# Discharge.net
KiCad netlist of a schematic drawn in Altium Designer
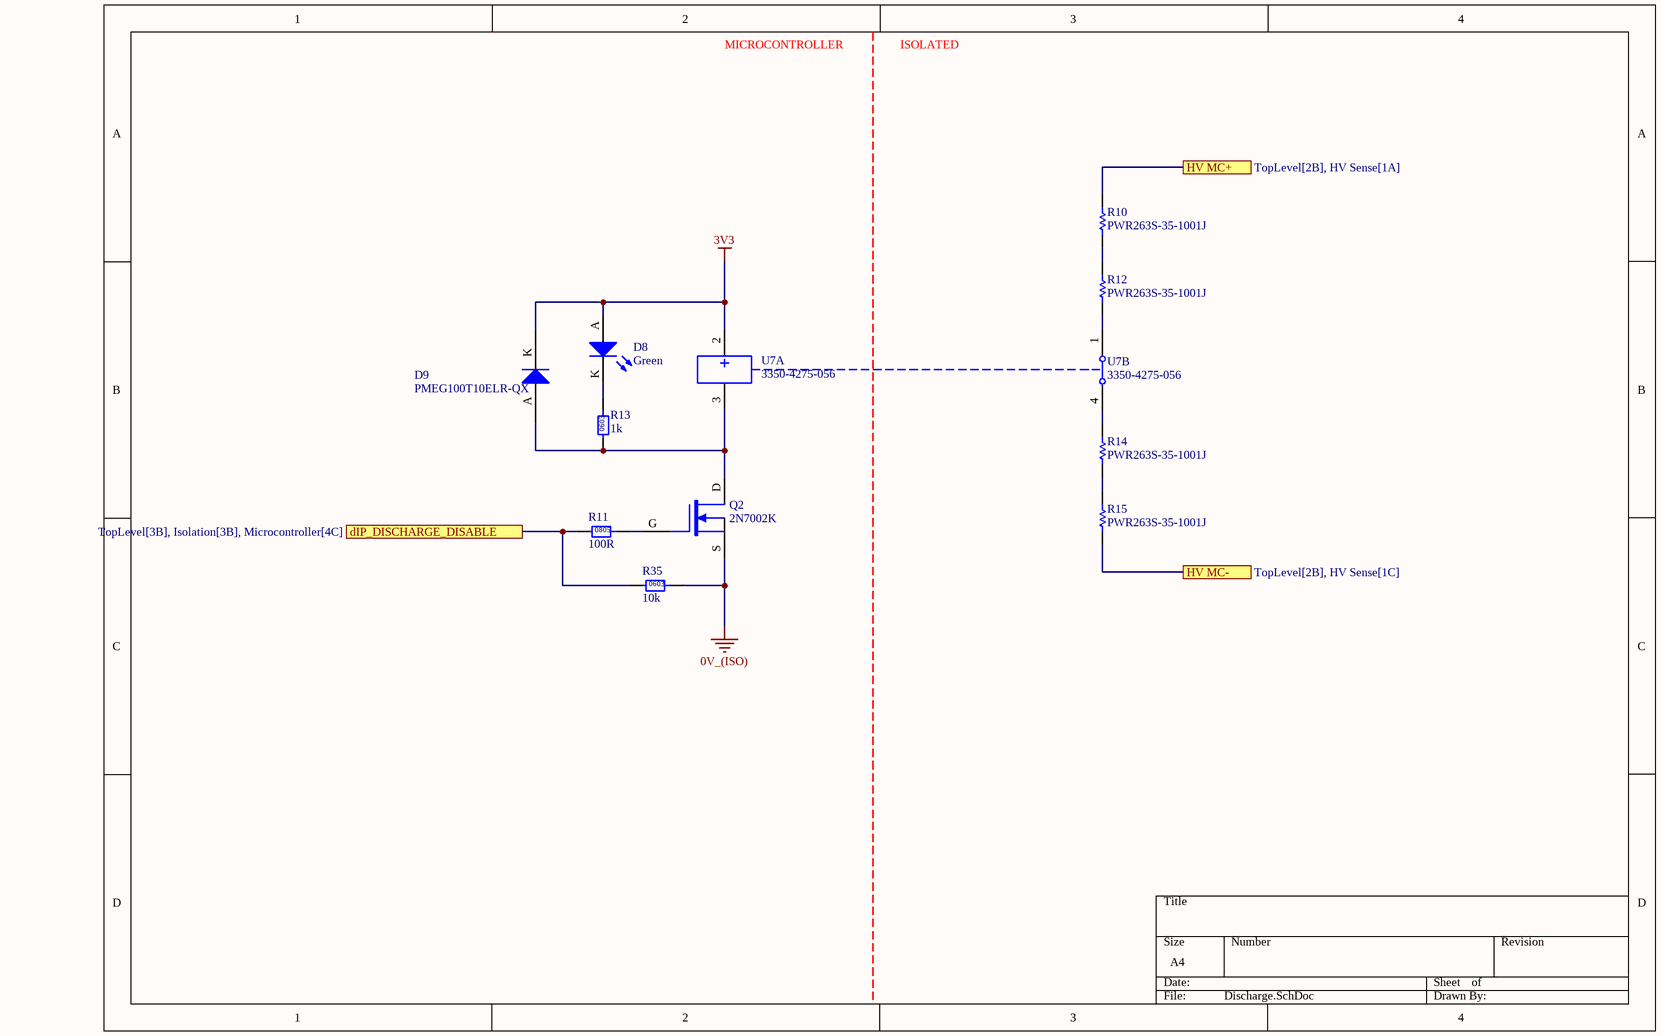
[diagram p0: Discharge.SchDoc]

(export (version "E")
  (design (tool "Eeschema 10.0.6"))
  (components
    (comp (ref "D8")
      (value "Green")
      (footprint "0805 LED")
      (description "Green LED Indication - Discrete 1.75V 0805 (2012 Metric)")
      (fields (field (name "PART NUMBER") "SML-210FTT86") (field (name "MANUFACTURER") "ROHM Semiconductor"))
      (libsource (lib "ts_standard_library") (part "LED"))
    )
    (comp (ref "D9")
      (value "PMEG100T10ELR-QX")
      (footprint "SODFL350X110-2N")
      (description "Diode 100 V 1A Surface Mount SOD-123W")
      (libsource (lib "Team Swinburne") (part "PMEG100T10ELR-QX"))
    )
    (comp (ref "Q2")
      (value "2N7002K")
      (footprint "2N7002K-Footprint-1")
      (description "60V 380mA, NFET MOSTFET (Small Signal)")
      (libsource (lib "Team Swinburne") (part "2N7002K"))
    )
    (comp (ref "R10")
      (value "PWR263S-35-1001J")
      (footprint "B TO-263")
      (fields
        (field (name "MANUFACTURER") "Bournes Inc")
        (field (name "TOLERANCE") "0.05")
        (field (name "DIGIKEY PART NUMBER") "PWR263S-35-1001J-ND")
      )
      (libsource (lib "Team Swinburne") (part "Resistor"))
    )
    (comp (ref "R11")
      (value "100R")
      (footprint "0805")
      (fields
        (field (name "PART NUMBER") "RC0805FR07100RL")
        (field (name "MANUFACTURER") "YAGEO")
        (field (name "TOLERANCE") "0.01")
      )
      (libsource (lib "ts_standard_library") (part "Resistor 0805"))
    )
    (comp (ref "R12")
      (value "PWR263S-35-1001J")
      (footprint "B TO-263")
      (fields
        (field (name "MANUFACTURER") "Bournes Inc")
        (field (name "TOLERANCE") "0.05")
        (field (name "DIGIKEY PART NUMBER") "PWR263S-35-1001J-ND")
      )
      (libsource (lib "Team Swinburne") (part "Resistor"))
    )
    (comp (ref "R13")
      (value "1k")
      (footprint "0603")
      (fields
        (field (name "PART NUMBER") "RC0603FR-071KL")
        (field (name "MANUFACTURER") "YAGEO")
        (field (name "TOLERANCE") "0.01")
      )
      (libsource (lib "ts_standard_library") (part "Resistor 0603"))
    )
    (comp (ref "R14")
      (value "PWR263S-35-1001J")
      (footprint "B TO-263")
      (fields
        (field (name "MANUFACTURER") "Bournes Inc")
        (field (name "TOLERANCE") "0.05")
        (field (name "DIGIKEY PART NUMBER") "PWR263S-35-1001J-ND")
      )
      (libsource (lib "Team Swinburne") (part "Resistor"))
    )
    (comp (ref "R15")
      (value "PWR263S-35-1001J")
      (footprint "B TO-263")
      (fields
        (field (name "MANUFACTURER") "Bournes Inc")
        (field (name "TOLERANCE") "0.05")
        (field (name "DIGIKEY PART NUMBER") "PWR263S-35-1001J-ND")
      )
      (libsource (lib "Team Swinburne") (part "Resistor"))
    )
    (comp (ref "R35")
      (value "10k")
      (footprint "0603")
      (fields
        (field (name "PART NUMBER") "RC0603FR-0710KL")
        (field (name "MANUFACTURER") "YAGEO")
        (field (name "TOLERANCE") "0.01")
      )
      (libsource (lib "ts_standard_library") (part "Resistor 0603"))
    )
    (comp (ref "U7")
      (value "3350-4275-056")
      (footprint "CI SPST")
      (description "RELAY REED HV SPST 200W 3A 5V (NC)")
      (libsource (lib "Team Swinburne") (part "3350-4275-056"))
    )
  )
  (nets
    (net (code "1") (name "/HV MC+") (class "Default")
      (node (ref "R10") (pin "1") (pinfunction "1_1") (pintype "passive"))
    )
    (net (code "2") (name "/HV MC-") (class "Default")
      (node (ref "R15") (pin "2") (pinfunction "2_2") (pintype "passive"))
    )
    (net (code "3") (name "/dIP_DISCHARGE_DISABLE") (class "Default")
      (node (ref "R11") (pin "1") (pinfunction "1_1") (pintype "passive"))
      (node (ref "R35") (pin "1") (pinfunction "1_1") (pintype "passive"))
    )
    (net (code "4") (name "0V_(ISO)") (class "Default")
      (node (ref "Q2") (pin "S") (pinfunction "S_S") (pintype "passive"))
      (node (ref "R35") (pin "2") (pinfunction "2_2") (pintype "passive"))
    )
    (net (code "5") (name "3V3") (class "Default")
      (node (ref "D8") (pin "A") (pinfunction "A_A") (pintype "passive"))
      (node (ref "D9") (pin "K") (pintype "passive"))
      (node (ref "U7") (pin "2") (pinfunction "2_2") (pintype "passive"))
    )
    (net (code "6") (name "Net-(D8-PadK)") (class "Default")
      (node (ref "D8") (pin "K") (pinfunction "K_K") (pintype "passive"))
      (node (ref "R13") (pin "2") (pinfunction "2_2") (pintype "passive"))
    )
    (net (code "7") (name "Net-(D9-PadA)") (class "Default")
      (node (ref "D9") (pin "A") (pintype "passive"))
      (node (ref "Q2") (pin "D") (pinfunction "D_D") (pintype "passive"))
      (node (ref "R13") (pin "1") (pinfunction "1_1") (pintype "passive"))
      (node (ref "U7") (pin "3") (pinfunction "3_3") (pintype "passive"))
    )
    (net (code "8") (name "Net-(Q2-PadG)") (class "Default")
      (node (ref "Q2") (pin "G") (pinfunction "G_G") (pintype "passive"))
      (node (ref "R11") (pin "2") (pinfunction "2_2") (pintype "passive"))
    )
    (net (code "9") (name "Net-(R10-Pad2)") (class "Default")
      (node (ref "R10") (pin "2") (pinfunction "2_2") (pintype "passive"))
      (node (ref "R12") (pin "1") (pinfunction "1_1") (pintype "passive"))
    )
    (net (code "10") (name "Net-(R12-Pad2)") (class "Default")
      (node (ref "R12") (pin "2") (pinfunction "2_2") (pintype "passive"))
      (node (ref "U7") (pin "1") (pinfunction "1_1") (pintype "passive"))
    )
    (net (code "11") (name "Net-(R14-Pad1)") (class "Default")
      (node (ref "R14") (pin "1") (pinfunction "1_1") (pintype "passive"))
      (node (ref "U7") (pin "4") (pinfunction "4_4") (pintype "passive"))
    )
    (net (code "12") (name "Net-(R14-Pad2)") (class "Default")
      (node (ref "R14") (pin "2") (pinfunction "2_2") (pintype "passive"))
      (node (ref "R15") (pin "1") (pinfunction "1_1") (pintype "passive"))
    )
  )
)
